# 05_SM32_MCU.net
KiCad netlist of a schematic drawn in Altium Designer
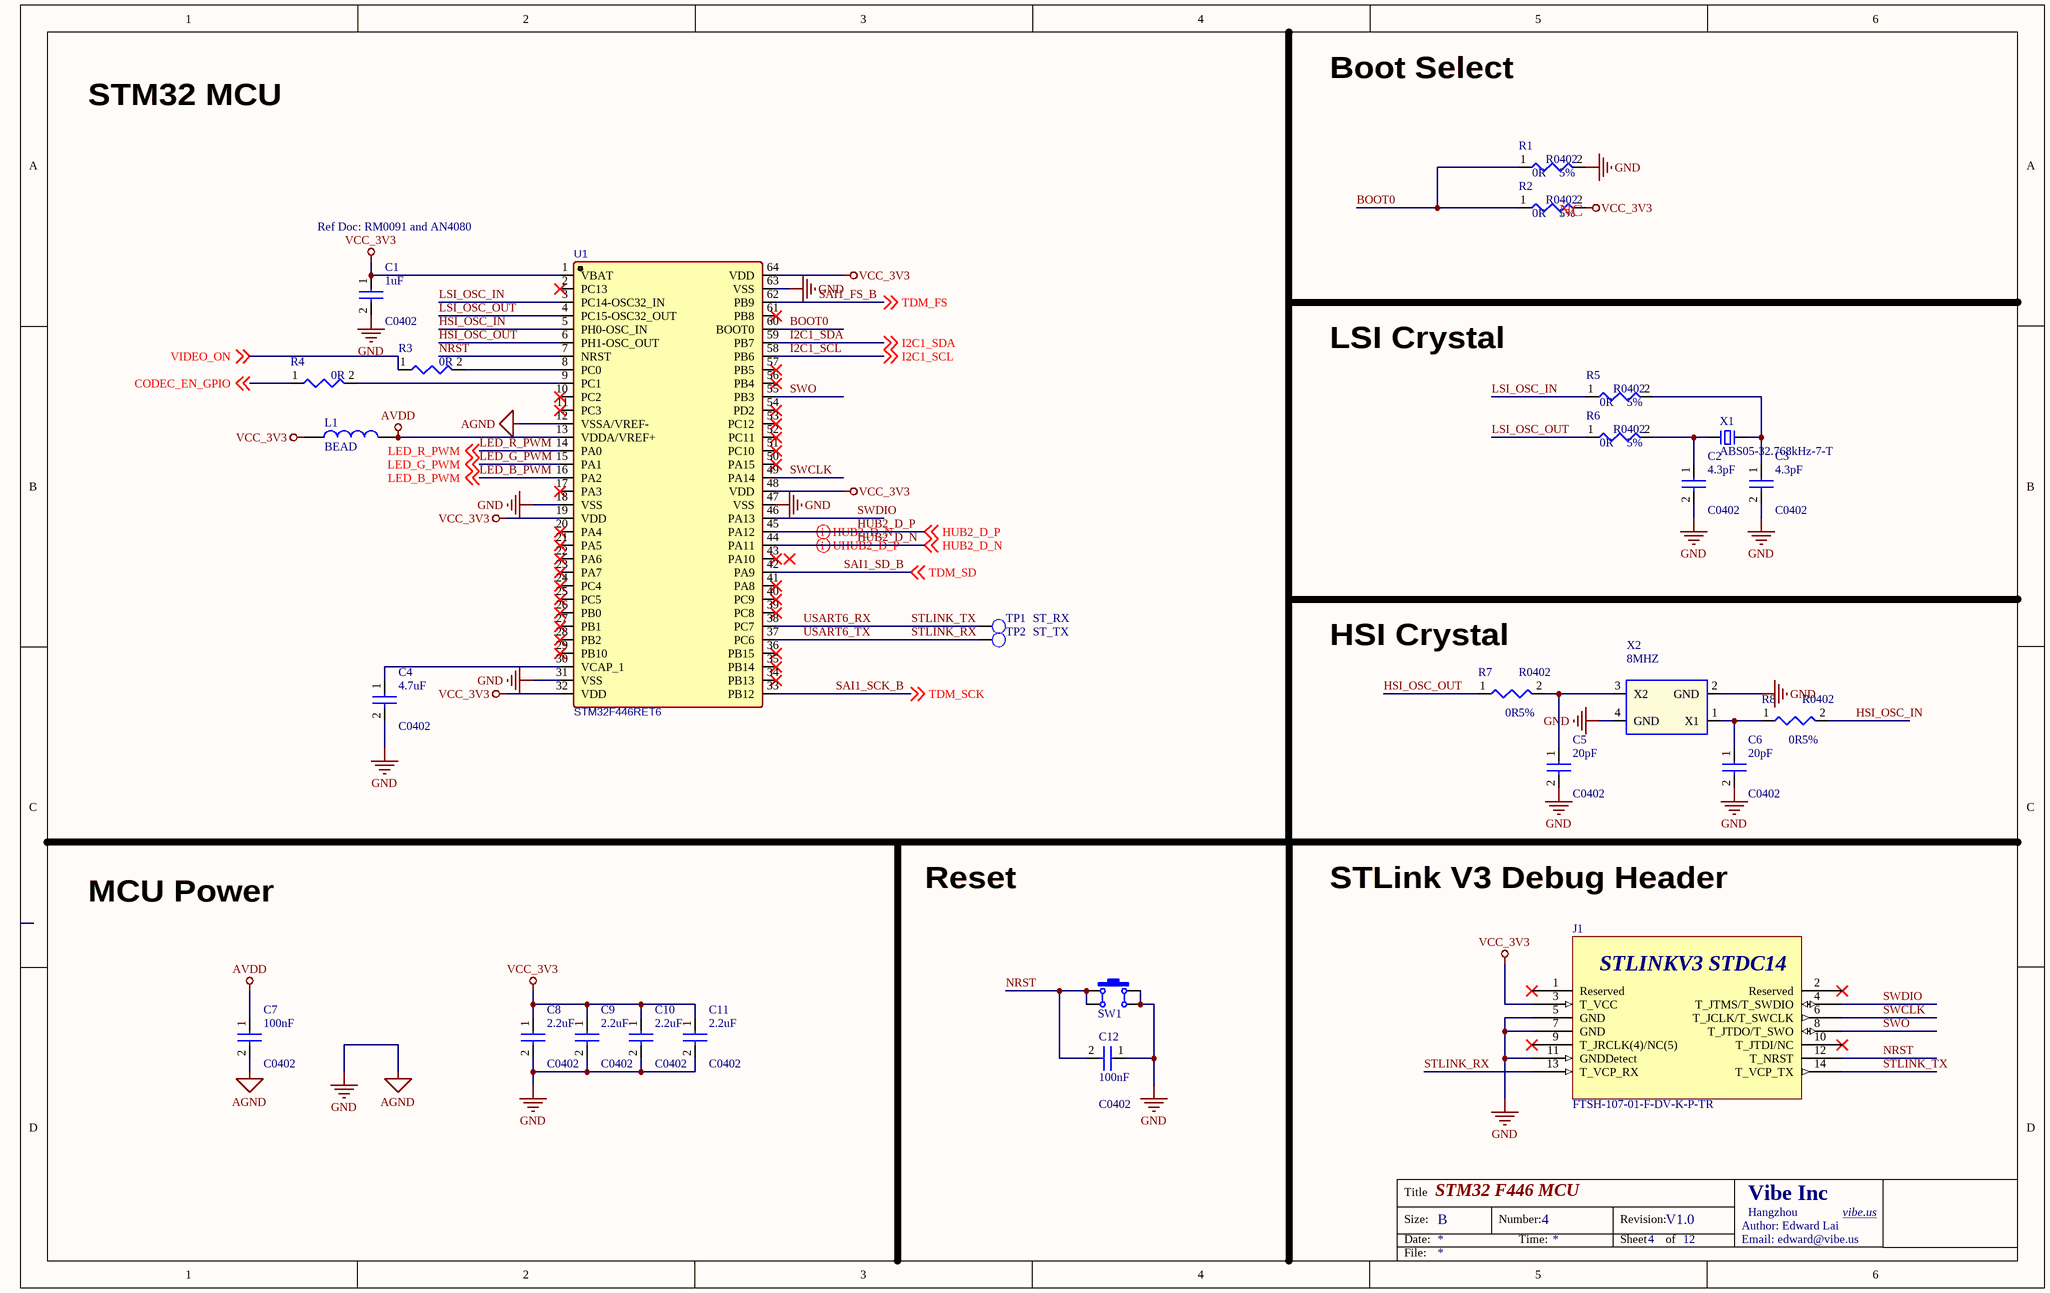
[diagram p0: 05_SM32_MCU.SchDoc]

(export (version "E")
  (design (tool "Eeschema 10.0.6"))
  (components
    (comp (ref "C1")
      (value "1uF")
      (footprint "C0402_L")
      (description "cap,1.00uF,+/-10%,10V,X5R,C0402")
      (fields (field (name "PCB FOOTPRINT") "C0402"))
      (libsource (lib "*") (part "CAP NP_Dup1"))
    )
    (comp (ref "C2")
      (value "4.3pF")
      (footprint "C0402_L")
      (description "cap,4.3pF,+/-10%,25V,X5R,C0402")
      (fields (field (name "PCB FOOTPRINT") "C0402"))
      (libsource (lib "*") (part "CAP NP_Dup1"))
    )
    (comp (ref "C3")
      (value "4.3pF")
      (footprint "C0402_L")
      (description "cap,4.3pF,+/-10%,25V,X5R,C0402")
      (fields (field (name "PCB FOOTPRINT") "C0402"))
      (libsource (lib "*") (part "CAP NP_Dup1"))
    )
    (comp (ref "C4")
      (value "4.7uF")
      (footprint "C0402_L")
      (description "cap,4.70uF,+/-10%,6.3V,X5R,C0402")
      (fields (field (name "PCB FOOTPRINT") "C0402"))
      (libsource (lib "*") (part "CAP NP_Dup1"))
    )
    (comp (ref "C5")
      (value "20pF")
      (footprint "C0402_L")
      (description "cap,20pF,+/-10%,25V,X5R,C0402")
      (fields (field (name "PCB FOOTPRINT") "C0402"))
      (libsource (lib "*") (part "CAP NP_Dup1"))
    )
    (comp (ref "C6")
      (value "20pF")
      (footprint "C0402_L")
      (description "cap,20pF,+/-10%,25V,X5R,C0402")
      (fields (field (name "PCB FOOTPRINT") "C0402"))
      (libsource (lib "*") (part "CAP NP_Dup1"))
    )
    (comp (ref "C7")
      (value "100nF")
      (footprint "C0402_L")
      (description "cap,100.00nF,+/-10%,10V,X5R,C0402")
      (fields (field (name "PCB FOOTPRINT") "C0402"))
      (libsource (lib "*") (part "CAP NP_Dup1"))
    )
    (comp (ref "C8")
      (value "2.2uF")
      (footprint "C0402_L")
      (description "cap,2.20uF,+/-10%,10V,X5R,C0402")
      (fields (field (name "PCB FOOTPRINT") "C0402"))
      (libsource (lib "*") (part "CAP NP_Dup1"))
    )
    (comp (ref "C9")
      (value "2.2uF")
      (footprint "C0402_L")
      (description "cap,2.20uF,+/-10%,10V,X5R,C0402")
      (fields (field (name "PCB FOOTPRINT") "C0402"))
      (libsource (lib "*") (part "CAP NP_Dup1"))
    )
    (comp (ref "C10")
      (value "2.2uF")
      (footprint "C0402_L")
      (description "cap,2.20uF,+/-10%,10V,X5R,C0402")
      (fields (field (name "PCB FOOTPRINT") "C0402"))
      (libsource (lib "*") (part "CAP NP_Dup1"))
    )
    (comp (ref "C11")
      (value "2.2uF")
      (footprint "C0402_L")
      (description "cap,2.20uF,+/-10%,10V,X5R,C0402")
      (fields (field (name "PCB FOOTPRINT") "C0402"))
      (libsource (lib "*") (part "CAP NP_Dup1"))
    )
    (comp (ref "C12")
      (value "100nF")
      (footprint "C0402_L")
      (description "cap,100.00nF,+/-10%,10V,X5R,C0402")
      (fields (field (name "PCB FOOTPRINT") "C0402"))
      (libsource (lib "*") (part "CAP NP_Dup1"))
    )
    (comp (ref "J1")
      (value "FTSH-107-01-F-DV-K-P-TR")
      (footprint "SAMTEC-FTSH-107-01-X-DV")
      (description "Samtec 14Pin 2x7 Header Connector.\r\nSTM32_STLINK_V3 Debug")
      (libsource (lib "Schlib1") (part "FTSH-107-01-F-DV-K-P-TR"))
    )
    (comp (ref "L1")
      (value "BEAD")
      (footprint "L0402")
      (description "鐵氧體磁珠 33ohm 0.55A 550mOhms 0402 Chip Bead")
      (libsource (lib "0.1 - 电阻-电容-电感-晶振-晶体-磁珠-电位器") (part "L-AL"))
    )
    (comp (ref "R1")
      (value "0R")
      (footprint "R0402")
      (description "通用厚膜电阻,0R,+/-5%,R0402")
      (fields (field (name "PCB FOOTPRINT") "R0402") (field (name "TOLERANCE") "5%"))
      (libsource (lib "*") (part "RESISTOR"))
    )
    (comp (ref "R2")
      (value "0R")
      (footprint "R0402")
      (description "通用厚膜电阻,0R,+/-5%,R0402")
      (fields (field (name "PCB FOOTPRINT") "R0402") (field (name "TOLERANCE") "5%"))
      (libsource (lib "*") (part "RESISTOR"))
    )
    (comp (ref "R3")
      (value "0R")
      (footprint "R0402")
      (description "通用厚膜电阻,0R,+/-5%,R0402")
      (fields (field (name "TOLERANCE") "5%"))
      (libsource (lib "*") (part "RESISTOR"))
    )
    (comp (ref "R4")
      (value "0R")
      (footprint "R0402")
      (description "通用厚膜电阻,0R,+/-5%,R0402")
      (fields (field (name "TOLERANCE") "5%"))
      (libsource (lib "*") (part "RESISTOR"))
    )
    (comp (ref "R5")
      (value "0R")
      (footprint "R0402")
      (description "通用厚膜电阻,0R,+/-5%,R0402")
      (fields (field (name "PCB FOOTPRINT") "R0402") (field (name "TOLERANCE") "5%"))
      (libsource (lib "*") (part "RESISTOR"))
    )
    (comp (ref "R6")
      (value "0R")
      (footprint "R0402")
      (description "通用厚膜电阻,0R,+/-5%,R0402")
      (fields (field (name "PCB FOOTPRINT") "R0402") (field (name "TOLERANCE") "5%"))
      (libsource (lib "*") (part "RESISTOR"))
    )
    (comp (ref "R7")
      (value "0R")
      (footprint "R0402")
      (description "通用厚膜电阻,0R,+/-5%,R0402")
      (fields (field (name "PCB FOOTPRINT") "R0402") (field (name "TOLERANCE") "5%"))
      (libsource (lib "*") (part "RESISTOR"))
    )
    (comp (ref "R8")
      (value "0R")
      (footprint "R0402")
      (description "通用厚膜电阻,0R,+/-5%,R0402")
      (fields (field (name "PCB FOOTPRINT") "R0402") (field (name "TOLERANCE") "5%"))
      (libsource (lib "*") (part "RESISTOR"))
    )
    (comp (ref "SW1")
      (value "4x4x1.5")
      (footprint "TSW SMD-6*6*5")
      (description "贴片4x4轻触开关")
      (libsource (lib "0.5 - 按键-开关-蜂鸣器-保险丝-电池-测试点-Mark点") (part "SW SMD-4x4"))
    )
    (comp (ref "TP1")
      (value "ST_RX")
      (footprint "TP_0R70")
      (description "Test Point 0.7mm")
      (libsource (lib "Schlib1") (part "TP"))
    )
    (comp (ref "TP2")
      (value "ST_TX")
      (footprint "TP_0R70")
      (description "Test Point 0.7mm")
      (libsource (lib "Schlib1") (part "TP"))
    )
    (comp (ref "U1")
      (value "STM32F446RET6")
      (footprint "LQFP64_L")
      (libsource (lib "2.7 - STM32 F4系列单片机") (part "STM32F446RET6"))
    )
    (comp (ref "X1")
      (value "ABS05-32.768kHz-7-T")
      (footprint "XTAL_3215-32.768K")
      (description "ABS05-32.768kHz-7-T\r\n3215 2脚无源晶振(谐振器）")
      (libsource (lib "0.1 - 电阻-电容-电感-晶振-晶体-磁珠-电位器") (part "XTAL-2P"))
    )
    (comp (ref "X2")
      (value "8MHZ")
      (footprint "XTAL_3225-8MHZ")
      (description "8MHZ (16pF), 3.2 mm x 2.5 mm\r\n无源晶振(谐振器）")
      (libsource (lib "*") (part "CRYSTAL_4P"))
    )
  )
  (nets
    (net (code "1") (name "/BOOT0") (class "Default")
      (node (ref "R1") (pin "1") (pinfunction "1_1") (pintype "passive"))
      (node (ref "R2") (pin "1") (pinfunction "1_1") (pintype "passive"))
      (node (ref "U1") (pin "60") (pinfunction "BOOT0_60") (pintype "passive"))
    )
    (net (code "2") (name "/HSI_OSC_IN") (class "Default")
      (node (ref "R8") (pin "2") (pinfunction "2_2") (pintype "passive"))
      (node (ref "U1") (pin "5") (pinfunction "PH0-OSC_IN_5") (pintype "passive"))
    )
    (net (code "3") (name "/HSI_OSC_OUT") (class "Default")
      (node (ref "R7") (pin "1") (pinfunction "1_1") (pintype "passive"))
      (node (ref "U1") (pin "6") (pinfunction "PH1-OSC_OUT_6") (pintype "passive"))
    )
    (net (code "4") (name "/LSI_OSC_IN") (class "Default")
      (node (ref "R5") (pin "1") (pinfunction "1_1") (pintype "passive"))
      (node (ref "U1") (pin "3") (pinfunction "PC14-OSC32_IN_3") (pintype "passive"))
    )
    (net (code "5") (name "/LSI_OSC_OUT") (class "Default")
      (node (ref "R6") (pin "1") (pinfunction "1_1") (pintype "passive"))
      (node (ref "U1") (pin "4") (pinfunction "PC15-OSC32_OUT_4") (pintype "passive"))
    )
    (net (code "6") (name "/NRST") (class "Default")
      (node (ref "C12") (pin "2") (pinfunction "2_2") (pintype "passive"))
      (node (ref "J1") (pin "12") (pinfunction "T_NRST_12") (pintype "passive"))
      (node (ref "SW1") (pin "1") (pinfunction "1_1") (pintype "passive"))
      (node (ref "SW1") (pin "4") (pinfunction "4_4") (pintype "passive"))
      (node (ref "U1") (pin "7") (pinfunction "NRST_7") (pintype "passive"))
    )
    (net (code "7") (name "/STLINK_RX") (class "Default")
      (node (ref "J1") (pin "13") (pinfunction "T_VCP_RX_13") (pintype "input"))
      (node (ref "TP2") (pin "1") (pinfunction "1_1") (pintype "passive"))
      (node (ref "U1") (pin "37") (pinfunction "PC6_37") (pintype "passive"))
    )
    (net (code "8") (name "/STLINK_TX") (class "Default")
      (node (ref "J1") (pin "14") (pinfunction "T_VCP_TX_14") (pintype "output"))
      (node (ref "TP1") (pin "1") (pinfunction "1_1") (pintype "passive"))
      (node (ref "U1") (pin "38") (pinfunction "PC7_38") (pintype "passive"))
    )
    (net (code "9") (name "/SWCLK") (class "Default")
      (node (ref "J1") (pin "6") (pinfunction "T_JCLK/T_SWCLK_6") (pintype "output"))
      (node (ref "U1") (pin "49") (pinfunction "PA14_49") (pintype "passive"))
    )
    (net (code "10") (name "/SWDIO") (class "Default")
      (node (ref "J1") (pin "4") (pinfunction "T_JTMS/T_SWDIO_4") (pintype "bidirectional"))
      (node (ref "U1") (pin "46") (pinfunction "PA13_46") (pintype "passive"))
    )
    (net (code "11") (name "/SWO") (class "Default")
      (node (ref "J1") (pin "8") (pinfunction "_T_JTDO/T_SWO_8") (pintype "bidirectional"))
      (node (ref "U1") (pin "55") (pinfunction "PB3_55") (pintype "passive"))
    )
    (net (code "12") (name "AGND") (class "Default")
      (node (ref "C1") (pin "2") (pinfunction "2_2") (pintype "passive"))
      (node (ref "C10") (pin "2") (pinfunction "2_2") (pintype "passive"))
      (node (ref "C11") (pin "2") (pinfunction "2_2") (pintype "passive"))
      (node (ref "C12") (pin "1") (pinfunction "1_1") (pintype "passive"))
      (node (ref "C2") (pin "2") (pinfunction "2_2") (pintype "passive"))
      (node (ref "C3") (pin "2") (pinfunction "2_2") (pintype "passive"))
      (node (ref "C4") (pin "2") (pinfunction "2_2") (pintype "passive"))
      (node (ref "C5") (pin "2") (pinfunction "2_2") (pintype "passive"))
      (node (ref "C6") (pin "2") (pinfunction "2_2") (pintype "passive"))
      (node (ref "C7") (pin "2") (pinfunction "2_2") (pintype "passive"))
      (node (ref "C8") (pin "2") (pinfunction "2_2") (pintype "passive"))
      (node (ref "C9") (pin "2") (pinfunction "2_2") (pintype "passive"))
      (node (ref "J1") (pin "11") (pinfunction "GNDDetect_11") (pintype "input"))
      (node (ref "J1") (pin "5") (pinfunction "GND_5") (pintype "passive"))
      (node (ref "J1") (pin "7") (pinfunction "GND_7") (pintype "passive"))
      (node (ref "R1") (pin "2") (pinfunction "2_2") (pintype "passive"))
      (node (ref "SW1") (pin "2") (pinfunction "2_2") (pintype "passive"))
      (node (ref "SW1") (pin "3") (pinfunction "3_3") (pintype "passive"))
      (node (ref "U1") (pin "12") (pinfunction "VSSA/VREF-_12") (pintype "passive"))
      (node (ref "U1") (pin "18") (pinfunction "VSS_18") (pintype "passive"))
      (node (ref "U1") (pin "31") (pinfunction "VSS_31") (pintype "passive"))
      (node (ref "U1") (pin "47") (pinfunction "VSS_47") (pintype "passive"))
      (node (ref "U1") (pin "63") (pinfunction "VSS_63") (pintype "passive"))
      (node (ref "X2") (pin "2") (pinfunction "GND_2") (pintype "power_in"))
      (node (ref "X2") (pin "4") (pinfunction "GND_4") (pintype "power_in"))
    )
    (net (code "13") (name "AVDD") (class "Default")
      (node (ref "C7") (pin "1") (pinfunction "1_1") (pintype "passive"))
      (node (ref "L1") (pin "2") (pinfunction "2_2") (pintype "passive"))
      (node (ref "U1") (pin "13") (pinfunction "VDDA/VREF+_13") (pintype "passive"))
    )
    (net (code "14") (name "CODEC_EN_GPIO") (class "Default")
      (node (ref "R4") (pin "1") (pinfunction "1_1") (pintype "passive"))
    )
    (net (code "15") (name "HUB2_D_N") (class "Default")
      (node (ref "U1") (pin "44") (pinfunction "PA11_44") (pintype "passive"))
    )
    (net (code "16") (name "HUB2_D_P") (class "Default")
      (node (ref "U1") (pin "45") (pinfunction "PA12_45") (pintype "passive"))
    )
    (net (code "17") (name "I2C1_SCL") (class "Default")
      (node (ref "U1") (pin "58") (pinfunction "PB6_58") (pintype "passive"))
    )
    (net (code "18") (name "I2C1_SDA") (class "Default")
      (node (ref "U1") (pin "59") (pinfunction "PB7_59") (pintype "passive"))
    )
    (net (code "19") (name "LED_B_PWM") (class "Default")
      (node (ref "U1") (pin "16") (pinfunction "PA2_16") (pintype "passive"))
    )
    (net (code "20") (name "LED_G_PWM") (class "Default")
      (node (ref "U1") (pin "15") (pinfunction "PA1_15") (pintype "passive"))
    )
    (net (code "21") (name "LED_R_PWM") (class "Default")
      (node (ref "U1") (pin "14") (pinfunction "PA0_14") (pintype "passive"))
    )
    (net (code "22") (name "Net-(C2-Pad1)") (class "Default")
      (node (ref "C2") (pin "1") (pinfunction "1_1") (pintype "passive"))
      (node (ref "R6") (pin "2") (pinfunction "2_2") (pintype "passive"))
      (node (ref "X1") (pin "1") (pinfunction "1_1") (pintype "passive"))
    )
    (net (code "23") (name "Net-(C3-Pad1)") (class "Default")
      (node (ref "C3") (pin "1") (pinfunction "1_1") (pintype "passive"))
      (node (ref "R5") (pin "2") (pinfunction "2_2") (pintype "passive"))
      (node (ref "X1") (pin "2") (pinfunction "2_2") (pintype "passive"))
    )
    (net (code "24") (name "Net-(U1-PC0)") (class "Default")
      (node (ref "R3") (pin "2") (pinfunction "2_2") (pintype "passive"))
      (node (ref "U1") (pin "8") (pinfunction "PC0_8") (pintype "passive"))
    )
    (net (code "25") (name "Net-(U1-PC1)") (class "Default")
      (node (ref "R4") (pin "2") (pinfunction "2_2") (pintype "passive"))
      (node (ref "U1") (pin "9") (pinfunction "PC1_9") (pintype "passive"))
    )
    (net (code "26") (name "Net-(U1-VCAP_1)") (class "Default")
      (node (ref "C4") (pin "1") (pinfunction "1_1") (pintype "passive"))
      (node (ref "U1") (pin "30") (pinfunction "VCAP_1_30") (pintype "passive"))
    )
    (net (code "27") (name "Net-(X2-X1)") (class "Default")
      (node (ref "C6") (pin "1") (pinfunction "1_1") (pintype "passive"))
      (node (ref "R8") (pin "1") (pinfunction "1_1") (pintype "passive"))
      (node (ref "X2") (pin "1") (pinfunction "X1_1") (pintype "passive"))
    )
    (net (code "28") (name "Net-(X2-X2)") (class "Default")
      (node (ref "C5") (pin "1") (pinfunction "1_1") (pintype "passive"))
      (node (ref "R7") (pin "2") (pinfunction "2_2") (pintype "passive"))
      (node (ref "X2") (pin "3") (pinfunction "X2_3") (pintype "passive"))
    )
    (net (code "29") (name "TDM_FS") (class "Default")
      (node (ref "U1") (pin "62") (pinfunction "PB9_62") (pintype "passive"))
    )
    (net (code "30") (name "TDM_SCK") (class "Default")
      (node (ref "U1") (pin "33") (pinfunction "PB12_33") (pintype "passive"))
    )
    (net (code "31") (name "TDM_SD") (class "Default")
      (node (ref "U1") (pin "42") (pinfunction "PA9_42") (pintype "passive"))
    )
    (net (code "32") (name "VCC_3V3") (class "Default")
      (node (ref "C1") (pin "1") (pinfunction "1_1") (pintype "passive"))
      (node (ref "C10") (pin "1") (pinfunction "1_1") (pintype "passive"))
      (node (ref "C11") (pin "1") (pinfunction "1_1") (pintype "passive"))
      (node (ref "C8") (pin "1") (pinfunction "1_1") (pintype "passive"))
      (node (ref "C9") (pin "1") (pinfunction "1_1") (pintype "passive"))
      (node (ref "J1") (pin "3") (pinfunction "T_VCC_3") (pintype "input"))
      (node (ref "L1") (pin "1") (pinfunction "1_1") (pintype "passive"))
      (node (ref "R2") (pin "2") (pinfunction "2_2") (pintype "passive"))
      (node (ref "U1") (pin "1") (pinfunction "VBAT_1") (pintype "passive"))
      (node (ref "U1") (pin "19") (pinfunction "VDD_19") (pintype "passive"))
      (node (ref "U1") (pin "32") (pinfunction "VDD_32") (pintype "passive"))
      (node (ref "U1") (pin "48") (pinfunction "VDD_48") (pintype "passive"))
      (node (ref "U1") (pin "64") (pinfunction "VDD_64") (pintype "passive"))
    )
    (net (code "33") (name "VIDEO_ON") (class "Default")
      (node (ref "R3") (pin "1") (pinfunction "1_1") (pintype "passive"))
    )
    (net (code "34") (name "unconnected-(J1-Reserved-Pad1)") (class "Default")
      (node (ref "J1") (pin "1") (pinfunction "Reserved_1") (pintype "passive+no_connect"))
    )
    (net (code "35") (name "unconnected-(J1-Reserved-Pad2)") (class "Default")
      (node (ref "J1") (pin "2") (pinfunction "Reserved_2") (pintype "passive+no_connect"))
    )
    (net (code "36") (name "unconnected-(J1-T_JRCLK(4){slash}NC(5)-Pad9)") (class "Default")
      (node (ref "J1") (pin "9") (pinfunction "T_JRCLK(4)/NC(5)_9") (pintype "passive+no_connect"))
    )
    (net (code "37") (name "unconnected-(J1-T_JTDI{slash}NC-Pad10)") (class "Default")
      (node (ref "J1") (pin "10") (pinfunction "T_JTDI/NC_10") (pintype "passive+no_connect"))
    )
    (net (code "38") (name "unconnected-(U1-PA3-Pad17)") (class "Default")
      (node (ref "U1") (pin "17") (pinfunction "PA3_17") (pintype "passive+no_connect"))
    )
    (net (code "39") (name "unconnected-(U1-PA4-Pad20)") (class "Default")
      (node (ref "U1") (pin "20") (pinfunction "PA4_20") (pintype "passive+no_connect"))
    )
    (net (code "40") (name "unconnected-(U1-PA5-Pad21)") (class "Default")
      (node (ref "U1") (pin "21") (pinfunction "PA5_21") (pintype "passive+no_connect"))
    )
    (net (code "41") (name "unconnected-(U1-PA6-Pad22)") (class "Default")
      (node (ref "U1") (pin "22") (pinfunction "PA6_22") (pintype "passive+no_connect"))
    )
    (net (code "42") (name "unconnected-(U1-PA7-Pad23)") (class "Default")
      (node (ref "U1") (pin "23") (pinfunction "PA7_23") (pintype "passive+no_connect"))
    )
    (net (code "43") (name "unconnected-(U1-PA8-Pad41)") (class "Default")
      (node (ref "U1") (pin "41") (pinfunction "PA8_41") (pintype "passive+no_connect"))
    )
    (net (code "44") (name "unconnected-(U1-PA10-Pad43)") (class "Default")
      (node (ref "U1") (pin "43") (pinfunction "PA10_43") (pintype "passive+no_connect"))
    )
    (net (code "45") (name "unconnected-(U1-PA15-Pad50)") (class "Default")
      (node (ref "U1") (pin "50") (pinfunction "PA15_50") (pintype "passive+no_connect"))
    )
    (net (code "46") (name "unconnected-(U1-PB0-Pad26)") (class "Default")
      (node (ref "U1") (pin "26") (pinfunction "PB0_26") (pintype "passive+no_connect"))
    )
    (net (code "47") (name "unconnected-(U1-PB1-Pad27)") (class "Default")
      (node (ref "U1") (pin "27") (pinfunction "PB1_27") (pintype "passive+no_connect"))
    )
    (net (code "48") (name "unconnected-(U1-PB2-Pad28)") (class "Default")
      (node (ref "U1") (pin "28") (pinfunction "PB2_28") (pintype "passive+no_connect"))
    )
    (net (code "49") (name "unconnected-(U1-PB4-Pad56)") (class "Default")
      (node (ref "U1") (pin "56") (pinfunction "PB4_56") (pintype "passive+no_connect"))
    )
    (net (code "50") (name "unconnected-(U1-PB5-Pad57)") (class "Default")
      (node (ref "U1") (pin "57") (pinfunction "PB5_57") (pintype "passive+no_connect"))
    )
    (net (code "51") (name "unconnected-(U1-PB8-Pad61)") (class "Default")
      (node (ref "U1") (pin "61") (pinfunction "PB8_61") (pintype "passive+no_connect"))
    )
    (net (code "52") (name "unconnected-(U1-PB10-Pad29)") (class "Default")
      (node (ref "U1") (pin "29") (pinfunction "PB10_29") (pintype "passive+no_connect"))
    )
    (net (code "53") (name "unconnected-(U1-PB13-Pad34)") (class "Default")
      (node (ref "U1") (pin "34") (pinfunction "PB13_34") (pintype "passive+no_connect"))
    )
    (net (code "54") (name "unconnected-(U1-PB14-Pad35)") (class "Default")
      (node (ref "U1") (pin "35") (pinfunction "PB14_35") (pintype "passive+no_connect"))
    )
    (net (code "55") (name "unconnected-(U1-PB15-Pad36)") (class "Default")
      (node (ref "U1") (pin "36") (pinfunction "PB15_36") (pintype "passive+no_connect"))
    )
    (net (code "56") (name "unconnected-(U1-PC2-Pad10)") (class "Default")
      (node (ref "U1") (pin "10") (pinfunction "PC2_10") (pintype "passive+no_connect"))
    )
    (net (code "57") (name "unconnected-(U1-PC3-Pad11)") (class "Default")
      (node (ref "U1") (pin "11") (pinfunction "PC3_11") (pintype "passive+no_connect"))
    )
    (net (code "58") (name "unconnected-(U1-PC4-Pad24)") (class "Default")
      (node (ref "U1") (pin "24") (pinfunction "PC4_24") (pintype "passive+no_connect"))
    )
    (net (code "59") (name "unconnected-(U1-PC5-Pad25)") (class "Default")
      (node (ref "U1") (pin "25") (pinfunction "PC5_25") (pintype "passive+no_connect"))
    )
    (net (code "60") (name "unconnected-(U1-PC8-Pad39)") (class "Default")
      (node (ref "U1") (pin "39") (pinfunction "PC8_39") (pintype "passive+no_connect"))
    )
    (net (code "61") (name "unconnected-(U1-PC9-Pad40)") (class "Default")
      (node (ref "U1") (pin "40") (pinfunction "PC9_40") (pintype "passive+no_connect"))
    )
    (net (code "62") (name "unconnected-(U1-PC10-Pad51)") (class "Default")
      (node (ref "U1") (pin "51") (pinfunction "PC10_51") (pintype "passive+no_connect"))
    )
    (net (code "63") (name "unconnected-(U1-PC11-Pad52)") (class "Default")
      (node (ref "U1") (pin "52") (pinfunction "PC11_52") (pintype "passive+no_connect"))
    )
    (net (code "64") (name "unconnected-(U1-PC12-Pad53)") (class "Default")
      (node (ref "U1") (pin "53") (pinfunction "PC12_53") (pintype "passive+no_connect"))
    )
    (net (code "65") (name "unconnected-(U1-PC13-Pad2)") (class "Default")
      (node (ref "U1") (pin "2") (pinfunction "PC13_2") (pintype "passive+no_connect"))
    )
    (net (code "66") (name "unconnected-(U1-PD2-Pad54)") (class "Default")
      (node (ref "U1") (pin "54") (pinfunction "PD2_54") (pintype "passive+no_connect"))
    )
  )
)
